# Fri3D_2020_02.net
KiCad netlist of a schematic drawn in Altium Designer
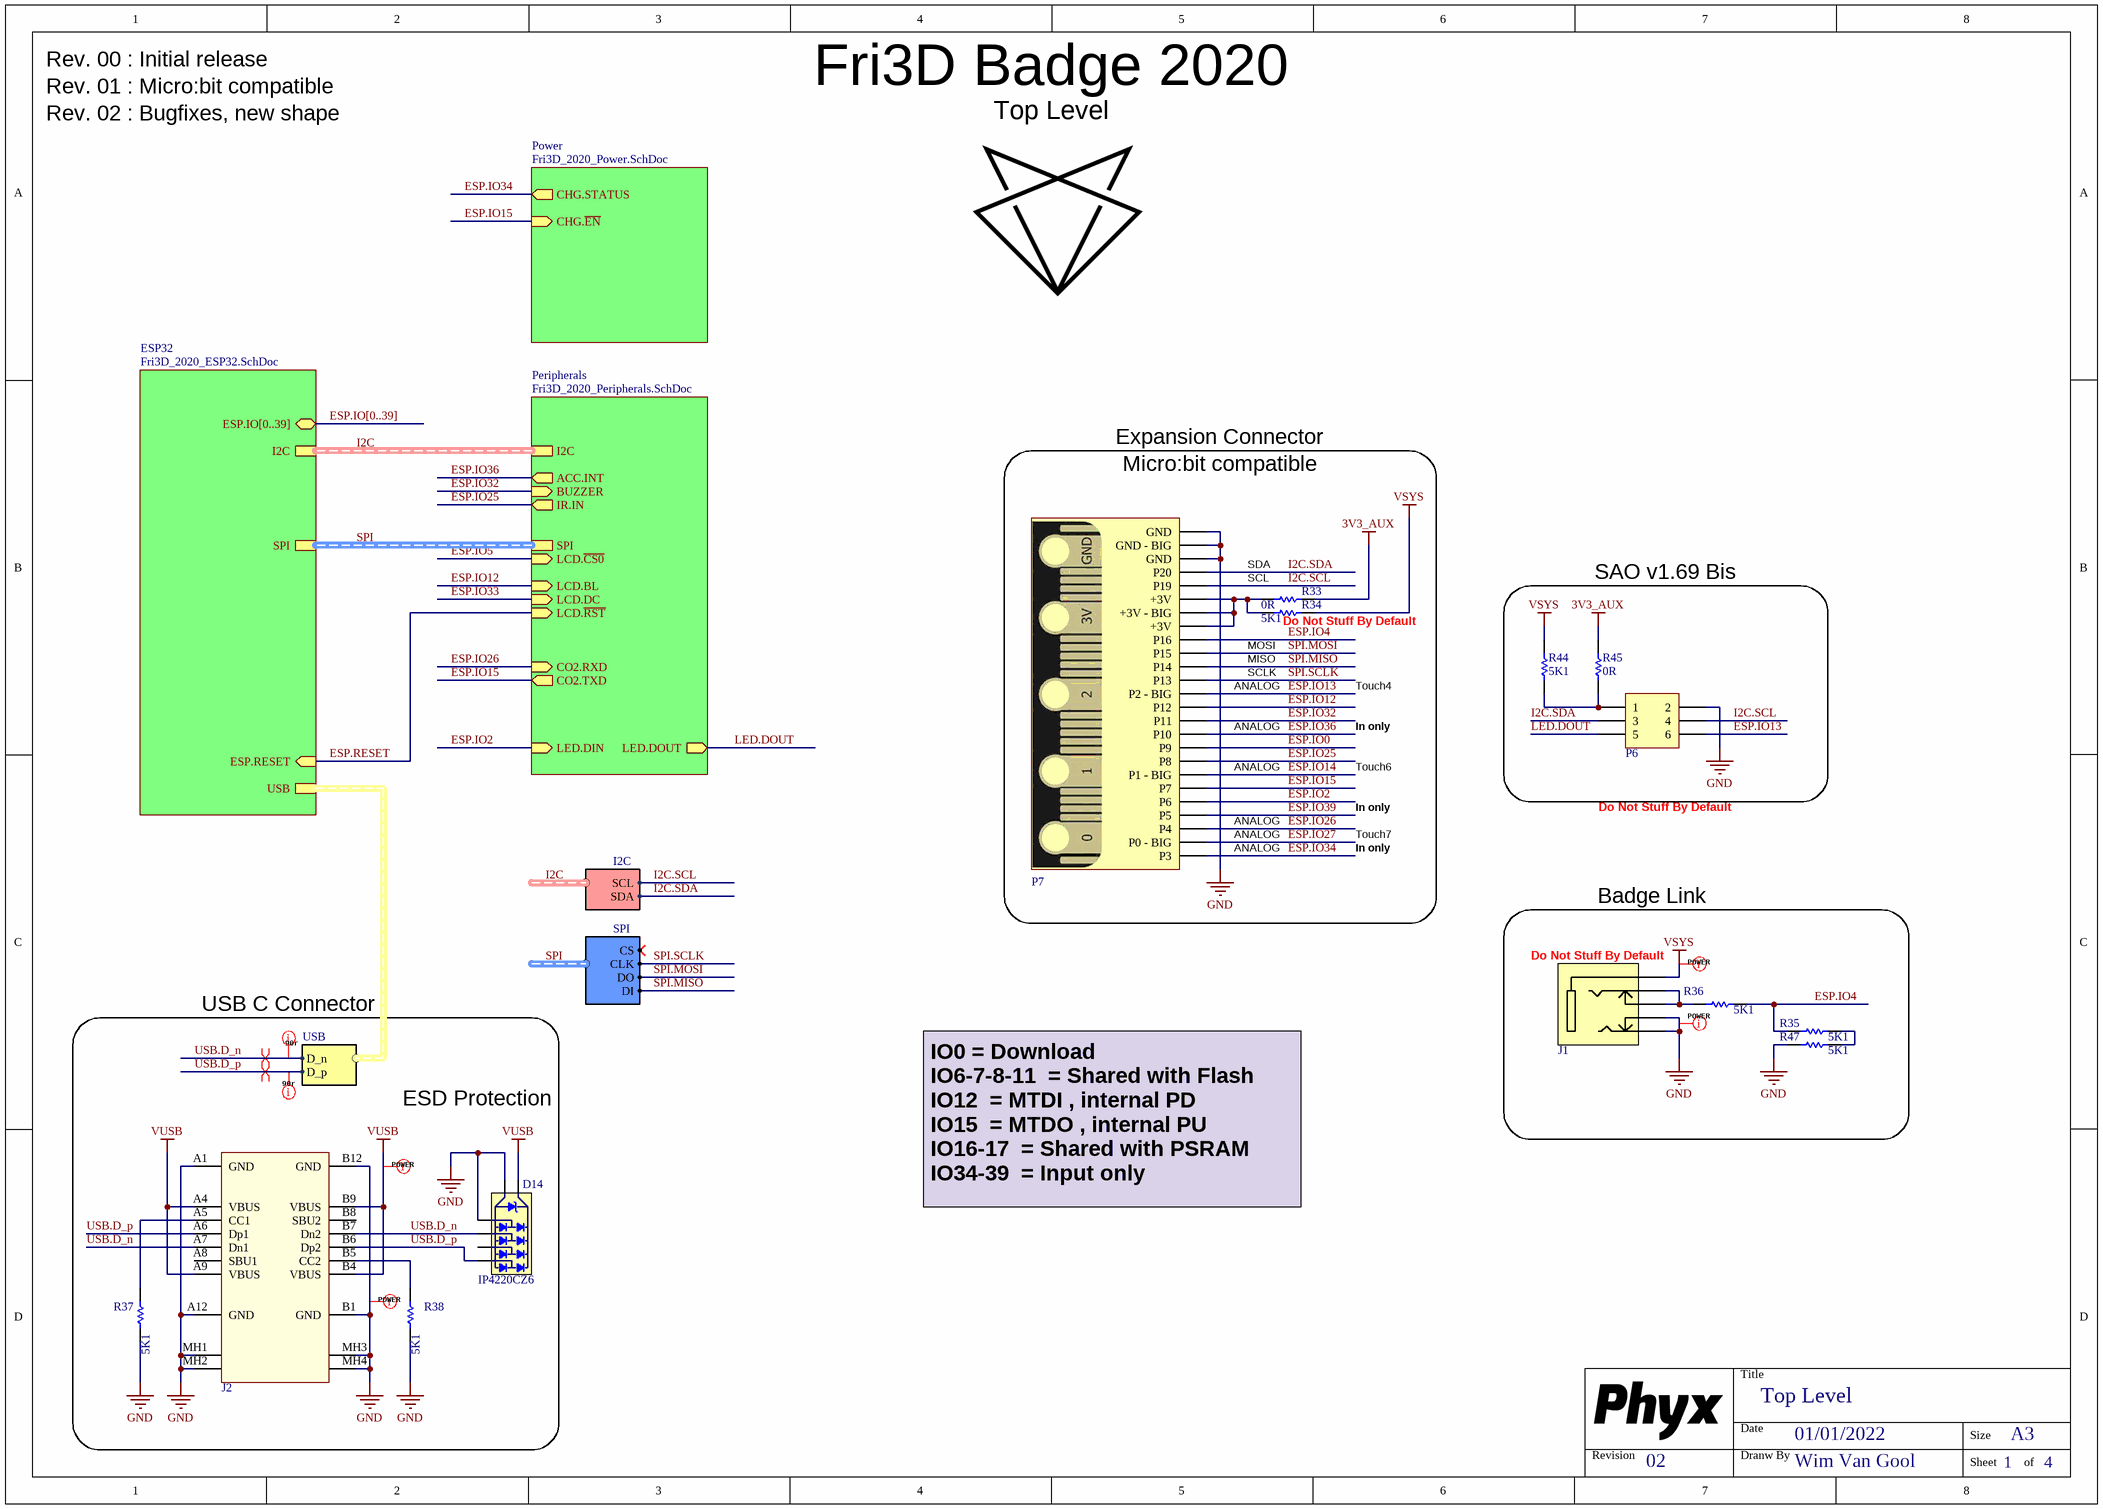
[diagram p0: Fri3D_2020_02.SchDoc]

(export (version "E")
  (design (tool "Eeschema 10.0.6"))
  (components
    (comp (ref "D14")
      (value "IP4220CZ6")
      (footprint "NXP_SOT457")
      (description "=Description")
      (fields (field (name "Comment") "TVS Diode Dual USB"))
      (libsource (lib "Phyx_Components") (part "NXP_IP4220CZ6"))
    )
    (comp (ref "J1")
      (value "3.5mm jack, dual switch, black, 3 contacts")
      (footprint "CUI_SJ1-3525NG")
      (description "=Description")
      (libsource (lib "Phyx_Components") (part "CUI_SJ1-3525NG"))
    )
    (comp (ref "J2")
      (value "USB 2.0 C Reversible Receptacle Horizontal")
      (footprint "HRO_TYPE-C-31-M-12")
      (libsource (lib "Phyx_Components") (part "USB_C_16_4"))
    )
    (comp (ref "P6")
      (value "Receptacle 3x2")
      (footprint "RCPT2X3")
      (libsource (lib "Phyx_Components") (part "Header 3X2"))
    )
    (comp (ref "P7")
      (value "MicroBit PCB connector")
      (footprint "MicroBIT_V2_PCB")
      (libsource (lib "Phyx_Components") (part "Header 25_MicroBit"))
    )
    (comp (ref "R33")
      (value "0R")
      (footprint "R0603_N")
      (fields (field (name "Comment") "RESISTOR"))
      (libsource (lib "Phyx_Components") (part "RESISTOR"))
    )
    (comp (ref "R34")
      (value "5K1")
      (footprint "R0603_N")
      (fields (field (name "Comment") "RESISTOR"))
      (libsource (lib "Phyx_Components") (part "RESISTOR"))
    )
    (comp (ref "R35")
      (value "5K1")
      (footprint "R0603_N")
      (fields (field (name "Comment") "RESISTOR"))
      (libsource (lib "Phyx_Components") (part "RESISTOR"))
    )
    (comp (ref "R36")
      (value "5K1")
      (footprint "R0603_N")
      (fields (field (name "Comment") "RESISTOR"))
      (libsource (lib "Phyx_Components") (part "RESISTOR"))
    )
    (comp (ref "R37")
      (value "5K1")
      (footprint "R0603_N")
      (fields (field (name "Comment") "RESISTOR"))
      (libsource (lib "Phyx_Components") (part "RESISTOR"))
    )
    (comp (ref "R38")
      (value "5K1")
      (footprint "R0603_N")
      (fields (field (name "Comment") "RESISTOR"))
      (libsource (lib "Phyx_Components") (part "RESISTOR"))
    )
    (comp (ref "R44")
      (value "5K1")
      (footprint "R0603_N")
      (fields (field (name "Comment") "RESISTOR"))
      (libsource (lib "Phyx_Components") (part "RESISTOR"))
    )
    (comp (ref "R45")
      (value "0R")
      (footprint "R0603_N")
      (fields (field (name "Comment") "RESISTOR"))
      (libsource (lib "Phyx_Components") (part "RESISTOR"))
    )
    (comp (ref "R47")
      (value "5K1")
      (footprint "R0603_N")
      (fields (field (name "Comment") "RESISTOR"))
      (libsource (lib "Phyx_Components") (part "RESISTOR"))
    )
  )
  (nets
    (net (code "31") (name "/ESP.IO0") (class "Default")
      (node (ref "P7") (pin "9") (pinfunction "P9_9") (pintype "passive"))
    )
    (net (code "32") (name "/ESP.IO2") (class "Default")
      (node (ref "P7") (pin "5") (pinfunction "P6_5") (pintype "passive"))
    )
    (net (code "33") (name "/ESP.IO4") (class "Default")
      (node (ref "P7") (pin "17") (pinfunction "P16_17") (pintype "passive"))
      (node (ref "R35") (pin "2") (pinfunction "2_2") (pintype "passive"))
      (node (ref "R36") (pin "1") (pinfunction "1_1") (pintype "passive"))
    )
    (net (code "35") (name "/ESP.IO12") (class "Default")
      (node (ref "P7") (pin "12") (pinfunction "P12_12") (pintype "passive"))
    )
    (net (code "36") (name "/ESP.IO13") (class "Default")
      (node (ref "P6") (pin "6") (pinfunction "6_6") (pintype "passive"))
      (node (ref "P7") (pin "13") (pinfunction "P2_-_BIG_13") (pintype "passive"))
    )
    (net (code "37") (name "/ESP.IO14") (class "Default")
      (node (ref "P7") (pin "7") (pinfunction "P1_-_BIG_7") (pintype "passive"))
    )
    (net (code "38") (name "/ESP.IO15") (class "Default")
      (node (ref "P7") (pin "6") (pinfunction "P7_6") (pintype "passive"))
    )
    (net (code "39") (name "/ESP.IO25") (class "Default")
      (node (ref "P7") (pin "8") (pinfunction "P8_8") (pintype "passive"))
    )
    (net (code "40") (name "/ESP.IO26") (class "Default")
      (node (ref "P7") (pin "3") (pinfunction "P4_3") (pintype "passive"))
    )
    (net (code "41") (name "/ESP.IO27") (class "Default")
      (node (ref "P7") (pin "2") (pinfunction "P0_-_BIG_2") (pintype "passive"))
    )
    (net (code "42") (name "/ESP.IO32") (class "Default")
      (node (ref "P7") (pin "11") (pinfunction "P11_11") (pintype "passive"))
    )
    (net (code "44") (name "/ESP.IO34") (class "Default")
      (node (ref "P7") (pin "1") (pinfunction "P3_1") (pintype "passive"))
    )
    (net (code "45") (name "/ESP.IO36") (class "Default")
      (node (ref "P7") (pin "10") (pinfunction "P10_10") (pintype "passive"))
    )
    (net (code "46") (name "/ESP.IO39") (class "Default")
      (node (ref "P7") (pin "4") (pinfunction "P5_4") (pintype "passive"))
    )
    (net (code "49") (name "/I2C.SCL") (class "Default")
      (node (ref "P6") (pin "4") (pinfunction "4_4") (pintype "passive"))
      (node (ref "P7") (pin "21") (pinfunction "P19_21") (pintype "passive"))
    )
    (net (code "50") (name "/I2C.SDA") (class "Default")
      (node (ref "P6") (pin "3") (pinfunction "3_3") (pintype "passive"))
      (node (ref "P7") (pin "22") (pinfunction "P20_22") (pintype "passive"))
    )
    (net (code "52") (name "/LED.DOUT") (class "Default")
      (node (ref "P6") (pin "5") (pinfunction "5_5") (pintype "passive"))
    )
    (net (code "53") (name "/SPI.MISO") (class "Default")
      (node (ref "P7") (pin "15") (pinfunction "P14_15") (pintype "passive"))
    )
    (net (code "54") (name "/SPI.MOSI") (class "Default")
      (node (ref "P7") (pin "16") (pinfunction "P15_16") (pintype "passive"))
    )
    (net (code "55") (name "/SPI.SCLK") (class "Default")
      (node (ref "P7") (pin "14") (pinfunction "P13_14") (pintype "passive"))
    )
    (net (code "57") (name "/USB.D_n") (class "Default")
      (node (ref "D14") (pin "1") (pinfunction "1_1") (pintype "passive"))
      (node (ref "J2") (pin "A7") (pinfunction "Dn1_A7") (pintype "passive"))
      (node (ref "J2") (pin "B7") (pinfunction "Dn2_B7") (pintype "passive"))
    )
    (net (code "58") (name "/USB.D_p") (class "Default")
      (node (ref "D14") (pin "6") (pinfunction "6_6") (pintype "passive"))
      (node (ref "J2") (pin "A6") (pinfunction "Dp1_A6") (pintype "passive"))
      (node (ref "J2") (pin "B6") (pinfunction "Dp2_B6") (pintype "passive"))
    )
    (net (code "62") (name "3V3_AUX") (class "Default")
      (node (ref "R33") (pin "1") (pinfunction "1_1") (pintype "passive"))
      (node (ref "R45") (pin "1") (pinfunction "1_1") (pintype "passive"))
    )
    (net (code "63") (name "GND") (class "Default")
      (node (ref "D14") (pin "2") (pinfunction "GND_2") (pintype "passive"))
      (node (ref "D14") (pin "3") (pinfunction "3_3") (pintype "passive"))
      (node (ref "J1") (pin "2") (pinfunction "Tip_2") (pintype "passive"))
      (node (ref "J1") (pin "4") (pinfunction "4_4") (pintype "passive"))
      (node (ref "J2") (pin "A1") (pinfunction "GND_A1") (pintype "passive"))
      (node (ref "J2") (pin "A12") (pinfunction "GND_A12") (pintype "passive"))
      (node (ref "J2") (pin "B1") (pinfunction "GND_B1") (pintype "passive"))
      (node (ref "J2") (pin "B12") (pinfunction "GND_B12") (pintype "passive"))
      (node (ref "J2") (pin "MH1") (pinfunction "Tab_MH1") (pintype "passive"))
      (node (ref "J2") (pin "MH2") (pinfunction "Tab_MH2") (pintype "passive"))
      (node (ref "J2") (pin "MH3") (pinfunction "Tab_MH3") (pintype "passive"))
      (node (ref "J2") (pin "MH4") (pinfunction "Tab_MH4") (pintype "passive"))
      (node (ref "P6") (pin "2") (pinfunction "2_2") (pintype "passive"))
      (node (ref "P7") (pin "23") (pinfunction "GND_23") (pintype "passive"))
      (node (ref "P7") (pin "24") (pinfunction "GND_-_BIG_24") (pintype "passive"))
      (node (ref "P7") (pin "25") (pinfunction "GND_25") (pintype "passive"))
      (node (ref "R37") (pin "2") (pinfunction "2_2") (pintype "passive"))
      (node (ref "R38") (pin "2") (pinfunction "2_2") (pintype "passive"))
      (node (ref "R47") (pin "2") (pinfunction "2_2") (pintype "passive"))
    )
    (net (code "64") (name "Net-(J1-Ring)") (class "Default")
      (node (ref "J1") (pin "3") (pinfunction "Ring_3") (pintype "passive"))
      (node (ref "J1") (pin "5") (pinfunction "5_5") (pintype "passive"))
      (node (ref "R36") (pin "2") (pinfunction "2_2") (pintype "passive"))
    )
    (net (code "65") (name "Net-(J2-CC1)") (class "Default")
      (node (ref "J2") (pin "A5") (pinfunction "CC1_A5") (pintype "passive"))
      (node (ref "R37") (pin "1") (pinfunction "1_1") (pintype "passive"))
    )
    (net (code "66") (name "Net-(J2-CC2)") (class "Default")
      (node (ref "J2") (pin "B5") (pinfunction "CC2_B5") (pintype "passive"))
      (node (ref "R38") (pin "1") (pinfunction "1_1") (pintype "passive"))
    )
    (net (code "67") (name "Net-(P6-Pad1)") (class "Default")
      (node (ref "P6") (pin "1") (pinfunction "1_1") (pintype "passive"))
      (node (ref "R44") (pin "1") (pinfunction "1_1") (pintype "passive"))
      (node (ref "R45") (pin "2") (pinfunction "2_2") (pintype "passive"))
    )
    (net (code "68") (name "Net-(P7-+3V_-_BIG)") (class "Default")
      (node (ref "P7") (pin "18") (pinfunction "+3V_18") (pintype "passive"))
      (node (ref "P7") (pin "19") (pinfunction "+3V_-_BIG_19") (pintype "passive"))
      (node (ref "P7") (pin "20") (pinfunction "+3V_20") (pintype "passive"))
      (node (ref "R33") (pin "2") (pinfunction "2_2") (pintype "passive"))
      (node (ref "R34") (pin "1") (pinfunction "1_1") (pintype "passive"))
    )
    (net (code "69") (name "Net-(R35-Pad1)") (class "Default")
      (node (ref "R35") (pin "1") (pinfunction "1_1") (pintype "passive"))
      (node (ref "R47") (pin "1") (pinfunction "1_1") (pintype "passive"))
    )
    (net (code "70") (name "VSYS") (class "Default")
      (node (ref "J1") (pin "1") (pinfunction "Sleeve_1") (pintype "passive"))
      (node (ref "R34") (pin "2") (pinfunction "2_2") (pintype "passive"))
      (node (ref "R44") (pin "2") (pinfunction "2_2") (pintype "passive"))
    )
    (net (code "71") (name "VUSB") (class "Default")
      (node (ref "D14") (pin "5") (pinfunction "VBus_5") (pintype "passive"))
      (node (ref "J2") (pin "A4") (pinfunction "VBUS_A4") (pintype "passive"))
      (node (ref "J2") (pin "A9") (pinfunction "VBUS_A9") (pintype "passive"))
      (node (ref "J2") (pin "B4") (pinfunction "VBUS_B4") (pintype "passive"))
      (node (ref "J2") (pin "B9") (pinfunction "VBUS_B9") (pintype "passive"))
    )
    (net (code "72") (name "unconnected-(D14-Pad4)") (class "Default")
      (node (ref "D14") (pin "4") (pinfunction "4_4") (pintype "passive"))
    )
    (net (code "73") (name "unconnected-(J2-SBU1-PadA8)") (class "Default")
      (node (ref "J2") (pin "A8") (pinfunction "SBU1_A8") (pintype "passive"))
    )
    (net (code "74") (name "unconnected-(J2-SBU2-PadB8)") (class "Default")
      (node (ref "J2") (pin "B8") (pinfunction "SBU2_B8") (pintype "passive"))
    )
  )
)
